# 5_LED_Voltage_Level_Meter.net
KiCad netlist of a schematic drawn in EAGLE
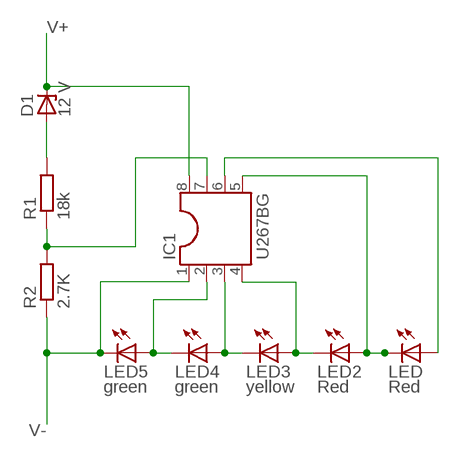
[diagram p0: schematic, sheet 1]

(export (version "E")
  (design (tool "Eeschema 10.0.6"))
  (components
    (comp (ref "D1")
      (value "12 V")
      (footprint "eagle-import:F126Z10")
      (libsource (lib "eagle-import") (part "ZENER-DIODEF126-10"))
    )
    (comp (ref "IC1")
      (value "U267BG")
      (footprint "eagle-import:DIL08")
      (libsource (lib "eagle-import") (part "DIL8"))
    )
    (comp (ref "LED")
      (value "Red")
      (footprint "eagle-import:LED3MM")
      (fields (field (name "MF") "VISHAY SEMICONDUCTOR") (field (name "OC_FARNELL") "1612437"))
      (libsource (lib "eagle-import") (part "TLLR4400"))
    )
    (comp (ref "LED2")
      (value "Red")
      (footprint "eagle-import:LED3MM")
      (fields (field (name "MF") "VISHAY SEMICONDUCTOR"))
      (libsource (lib "eagle-import") (part "TLLR4400"))
    )
    (comp (ref "LED3")
      (value "yellow")
      (footprint "eagle-import:LED3MM")
      (fields (field (name "MF") "VISHAY SEMICONDUCTOR"))
      (libsource (lib "eagle-import") (part "TLLY4400"))
    )
    (comp (ref "LED4")
      (value "green")
      (footprint "eagle-import:LED3MM")
      (fields (field (name "MF") "VISHAY SEMICONDUCTOR"))
      (libsource (lib "eagle-import") (part "TLLG4400"))
    )
    (comp (ref "LED5")
      (value "green")
      (footprint "eagle-import:LED3MM")
      (fields (field (name "MF") "VISHAY SEMICONDUCTOR"))
      (libsource (lib "eagle-import") (part "TLLG4400"))
    )
    (comp (ref "R1")
      (value "18k")
      (footprint "eagle-import:0207_12")
      (libsource (lib "eagle-import") (part "R-EU_0207/12"))
    )
    (comp (ref "R2")
      (value "2.7K")
      (footprint "eagle-import:0207_10")
      (libsource (lib "eagle-import") (part "R-EU_0207/10"))
    )
  )
  (nets
    (net (code "1") (name "/V+") (class "Default")
      (node (ref "D1") (pin "C") (pinfunction "C_C") (pintype "passive"))
      (node (ref "IC1") (pin "8") (pinfunction "8_8") (pintype "passive"))
    )
    (net (code "2") (name "/V-") (class "Default")
      (node (ref "IC1") (pin "1") (pinfunction "1_1") (pintype "passive"))
      (node (ref "LED5") (pin "K") (pinfunction "C_K") (pintype "passive"))
      (node (ref "R2") (pin "1") (pinfunction "1_1") (pintype "passive"))
    )
    (net (code "3") (name "Net-(D1-PadA)") (class "Default")
      (node (ref "D1") (pin "A") (pinfunction "A_A") (pintype "passive"))
      (node (ref "R1") (pin "2") (pinfunction "2_2") (pintype "passive"))
    )
    (net (code "4") (name "Net-(IC1-Pad6)") (class "Default")
      (node (ref "IC1") (pin "6") (pinfunction "6_6") (pintype "passive"))
      (node (ref "LED") (pin "A") (pinfunction "A_A") (pintype "passive"))
    )
    (net (code "5") (name "Net-(IC1-Pad7)") (class "Default")
      (node (ref "IC1") (pin "7") (pinfunction "7_7") (pintype "passive"))
      (node (ref "R1") (pin "1") (pinfunction "1_1") (pintype "passive"))
      (node (ref "R2") (pin "2") (pinfunction "2_2") (pintype "passive"))
    )
    (net (code "6") (name "Net-(LED-C)") (class "Default")
      (node (ref "IC1") (pin "5") (pinfunction "5_5") (pintype "passive"))
      (node (ref "LED") (pin "K") (pinfunction "C_K") (pintype "passive"))
      (node (ref "LED2") (pin "A") (pinfunction "A_A") (pintype "passive"))
    )
    (net (code "7") (name "Net-(LED2-C)") (class "Default")
      (node (ref "IC1") (pin "4") (pinfunction "4_4") (pintype "passive"))
      (node (ref "LED2") (pin "K") (pinfunction "C_K") (pintype "passive"))
      (node (ref "LED3") (pin "A") (pinfunction "A_A") (pintype "passive"))
    )
    (net (code "8") (name "Net-(LED3-C)") (class "Default")
      (node (ref "IC1") (pin "3") (pinfunction "3_3") (pintype "passive"))
      (node (ref "LED3") (pin "K") (pinfunction "C_K") (pintype "passive"))
      (node (ref "LED4") (pin "A") (pinfunction "A_A") (pintype "passive"))
    )
    (net (code "9") (name "Net-(LED4-C)") (class "Default")
      (node (ref "IC1") (pin "2") (pinfunction "2_2") (pintype "passive"))
      (node (ref "LED4") (pin "K") (pinfunction "C_K") (pintype "passive"))
      (node (ref "LED5") (pin "A") (pinfunction "A_A") (pintype "passive"))
    )
  )
)
